# HVBlocks.net
KiCad netlist of a schematic drawn in Altium Designer
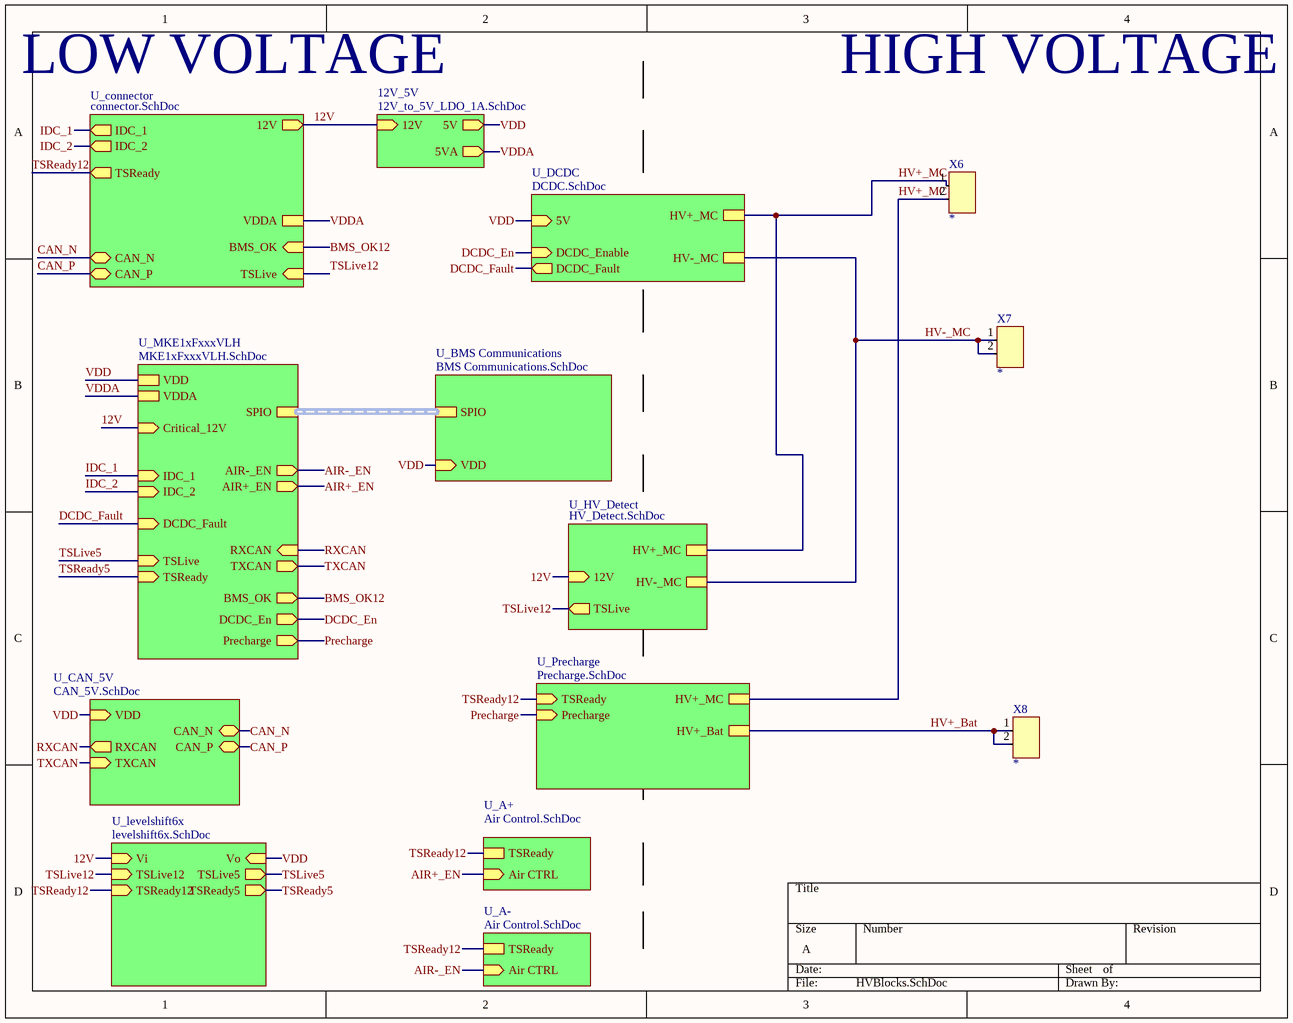
[diagram p0: HVBlocks.SchDoc]

(export (version "E")
  (design (tool "Eeschema 10.0.6"))
  (components
    (comp (ref "X6")
      (value "*")
      (footprint "CONN 43650-0200 MOLEX 2PIN")
      (description "Molex 43650_0200")
      (libsource (lib "altlib") (part "CONN 2POS"))
    )
    (comp (ref "X7")
      (value "*")
      (footprint "CONN 43650-0200 MOLEX 2PIN")
      (description "Molex 43650_0200")
      (libsource (lib "altlib") (part "CONN 2POS"))
    )
    (comp (ref "X8")
      (value "*")
      (footprint "CONN 43650-0200 MOLEX 2PIN")
      (description "Molex 43650_0200")
      (libsource (lib "altlib") (part "CONN 2POS"))
    )
  )
  (nets
    (net (code "9") (name "/HV+_Bat") (class "Default")
      (node (ref "X8") (pin "1") (pintype "passive"))
      (node (ref "X8") (pin "2") (pintype "passive"))
    )
    (net (code "10") (name "/HV+_MC") (class "Default")
      (node (ref "X6") (pin "1") (pintype "passive"))
      (node (ref "X6") (pin "2") (pintype "passive"))
    )
    (net (code "11") (name "/HV-_MC") (class "Default")
      (node (ref "X7") (pin "1") (pintype "passive"))
      (node (ref "X7") (pin "2") (pintype "passive"))
    )
  )
)
